# asserv1.net
KiCad netlist of a schematic drawn in Altium Designer
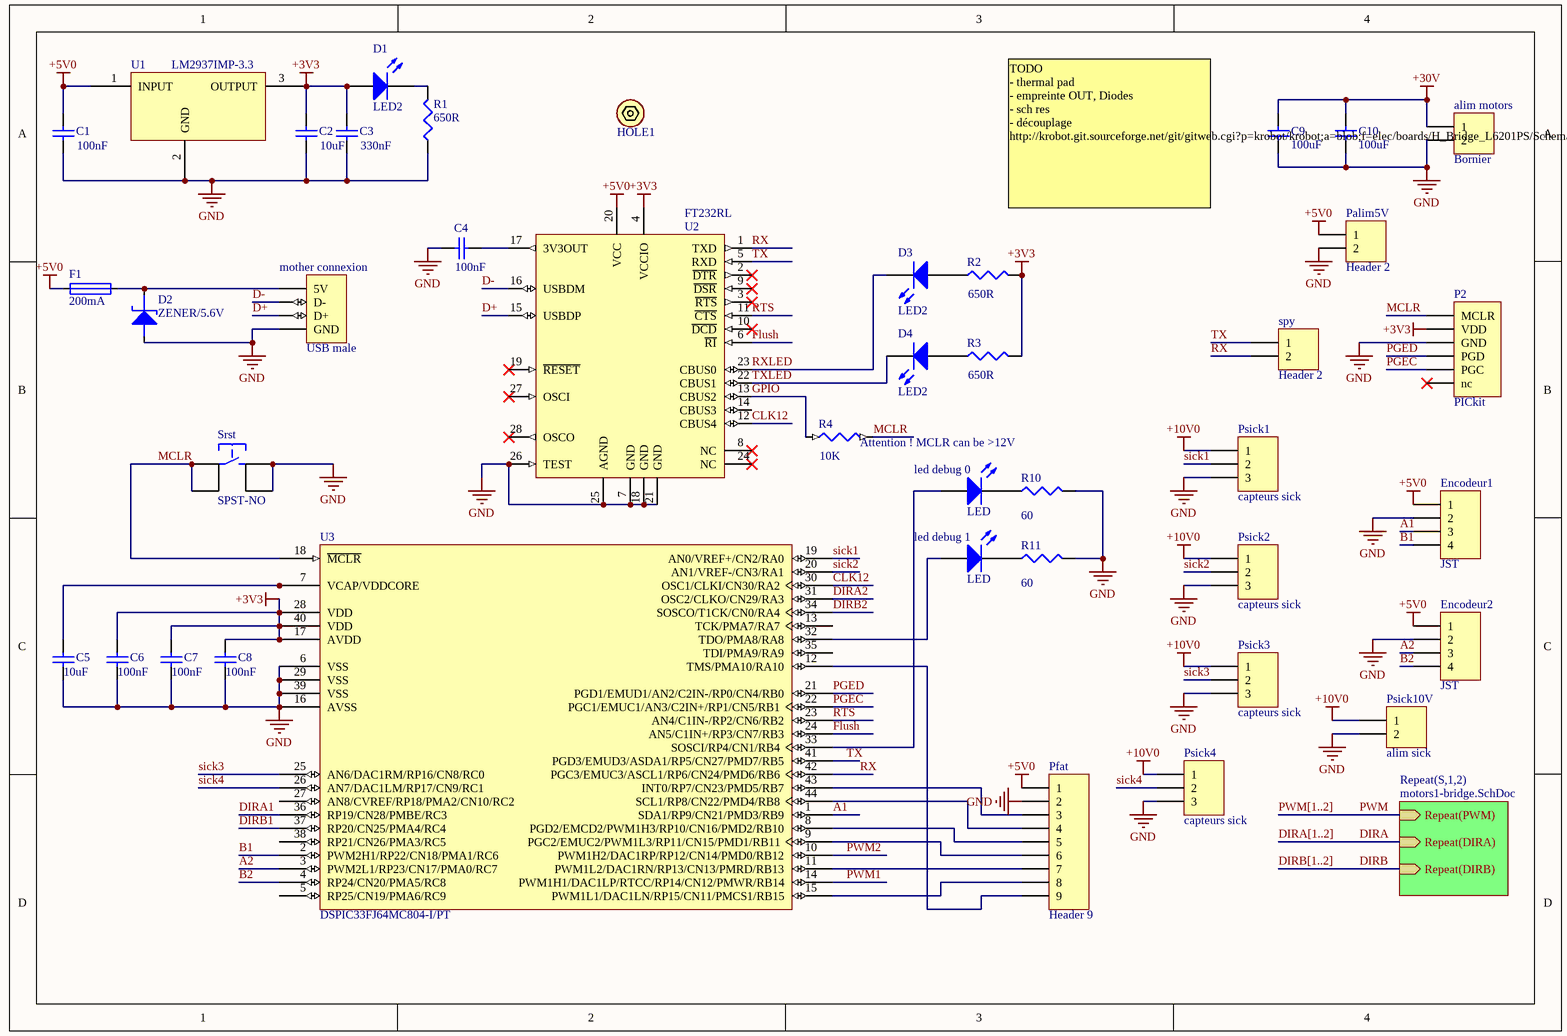
[diagram p0: asserv1.SchDoc]

(export (version "E")
  (design (tool "Eeschema 10.0.6"))
  (components
    (comp (ref "alim motors")
      (value "Bornier")
      (footprint "Bornier male coude 2 voies")
      (description "Header, 2-Pin")
      (fields (field (name "PUBLISHER") "Altium Limited"))
      (libsource (lib "7Robot") (part "Header 2"))
    )
    (comp (ref "C1")
      (value "100nF")
      (footprint "C0805C")
      (description "Capacitor (Semiconductor SIM Model)")
      (fields (field (name "PUBLISHER") "Altium Limited"))
      (libsource (lib "Miscellaneous Devices") (part "Cap Semi"))
    )
    (comp (ref "C2")
      (value "10uF")
      (footprint "C0805C")
      (description "Capacitor (Semiconductor SIM Model)")
      (fields (field (name "PUBLISHER") "Altium Limited"))
      (libsource (lib "Miscellaneous Devices") (part "Cap Semi"))
    )
    (comp (ref "C3")
      (value "330nF")
      (footprint "C0805C")
      (description "Capacitor (Semiconductor SIM Model)")
      (fields (field (name "PUBLISHER") "Altium Limited"))
      (libsource (lib "Miscellaneous Devices") (part "Cap Semi"))
    )
    (comp (ref "C4")
      (value "100nF")
      (footprint "C0805C")
      (description "Capacitor (Semiconductor SIM Model)")
      (fields (field (name "PUBLISHER") "Altium Limited"))
      (libsource (lib "Miscellaneous Devices") (part "Cap Semi"))
    )
    (comp (ref "C5")
      (value "10uF")
      (footprint "C0805C")
      (description "Capacitor (Semiconductor SIM Model)")
      (fields (field (name "PUBLISHER") "Altium Limited"))
      (libsource (lib "Miscellaneous Devices") (part "Cap Semi"))
    )
    (comp (ref "C6")
      (value "100nF")
      (footprint "C0805C")
      (description "Capacitor (Semiconductor SIM Model)")
      (fields (field (name "PUBLISHER") "Altium Limited"))
      (libsource (lib "Miscellaneous Devices") (part "Cap Semi"))
    )
    (comp (ref "C7")
      (value "100nF")
      (footprint "C0805C")
      (description "Capacitor (Semiconductor SIM Model)")
      (fields (field (name "PUBLISHER") "Altium Limited"))
      (libsource (lib "Miscellaneous Devices") (part "Cap Semi"))
    )
    (comp (ref "C8")
      (value "100nF")
      (footprint "C0805C")
      (description "Capacitor (Semiconductor SIM Model)")
      (fields (field (name "PUBLISHER") "Altium Limited"))
      (libsource (lib "Miscellaneous Devices") (part "Cap Semi"))
    )
    (comp (ref "C9")
      (value "100uF")
      (footprint "Capacitor axial leaded")
      (description "Capacitor")
      (fields (field (name "Comment") "CAP") (field (name "PUBLISHER") "Altium Limited"))
      (libsource (lib "7Robot") (part "CAP"))
    )
    (comp (ref "C10")
      (value "100uF")
      (footprint "Capacitor axial leaded")
      (description "Capacitor")
      (fields (field (name "Comment") "CAP") (field (name "PUBLISHER") "Altium Limited"))
      (libsource (lib "7Robot") (part "CAP"))
    )
    (comp (ref "D1")
      (value "LED2")
      (footprint "LED1206G")
      (description "Typical RED, GREEN, YELLOW, AMBER GaAs LED")
      (fields (field (name "PUBLISHER") "Altium Limited"))
      (libsource (lib "7Robot") (part "LED2"))
    )
    (comp (ref "D2")
      (value "ZENER/5.6V")
      (footprint "DSO-C2/X1.8")
      (description "ZENER")
      (libsource (lib "7Robot") (part "ZENER"))
    )
    (comp (ref "D3")
      (value "LED2")
      (footprint "LED1206Y")
      (description "Typical RED, GREEN, YELLOW, AMBER GaAs LED")
      (fields (field (name "PUBLISHER") "Altium Limited"))
      (libsource (lib "7Robot") (part "LED2"))
    )
    (comp (ref "D4")
      (value "LED2")
      (footprint "LED1206Y")
      (description "Typical RED, GREEN, YELLOW, AMBER GaAs LED")
      (fields (field (name "PUBLISHER") "Altium Limited"))
      (libsource (lib "7Robot") (part "LED2"))
    )
    (comp (ref "Encodeur1")
      (value "JST")
      (footprint "B4B-PH-K-S")
      (description "Header, 4-Pin")
      (fields (field (name "PUBLISHER") "Altium Limited"))
      (libsource (lib "Miscellaneous Connectors") (part "Header 4"))
    )
    (comp (ref "Encodeur2")
      (value "JST")
      (footprint "B4B-PH-K-S")
      (description "Header, 4-Pin")
      (fields (field (name "PUBLISHER") "Altium Limited"))
      (libsource (lib "Miscellaneous Connectors") (part "Header 4"))
    )
    (comp (ref "F1")
      (value "200mA")
      (footprint "Fuse Holder 5x20mm")
      (libsource (lib "gini_base_sch") (part "FUSE1"))
    )
    (comp (ref "HOLE1")
      (value "Hole")
      (footprint "SCREW")
      (description "Mounting Hole for screws")
      (libsource (lib "7Robot") (part "Hole"))
    )
    (comp (ref "led debug 0")
      (value "LED")
      (footprint "LED1206R")
      (description "Typical RED, GREEN, YELLOW, AMBER GaAs LED")
      (fields (field (name "PUBLISHER") "Altium Limited"))
      (libsource (lib "7Robot") (part "LED2"))
    )
    (comp (ref "led debug 1")
      (value "LED")
      (footprint "LED1206R")
      (description "Typical RED, GREEN, YELLOW, AMBER GaAs LED")
      (fields (field (name "PUBLISHER") "Altium Limited"))
      (libsource (lib "7Robot") (part "LED2"))
    )
    (comp (ref "mother connexion")
      (value "USB male")
      (footprint "USB SM2.5 Male")
      (description "USB Connector")
      (fields (field (name "PUBLISHER") "Altium Limited"))
      (libsource (lib "7Robot") (part "USB Con"))
    )
    (comp (ref "P2")
      (value "PICkit")
      (footprint "HDR1X6H")
      (description "Header, 6-Pin, Right Angle")
      (fields (field (name "PUBLISHER") "Altium Limited"))
      (libsource (lib "7Robot") (part "Header ICSP"))
    )
    (comp (ref "Palim5V")
      (value "Header 2")
      (footprint "Bornier male coude 2 voies")
      (description "Header, 2-Pin")
      (fields (field (name "PUBLISHER") "Altium Limited"))
      (libsource (lib "7Robot") (part "Header 2"))
    )
    (comp (ref "Pfat")
      (value "Header 9")
      (footprint "HDR1X9")
      (description "Header, 9-Pin")
      (fields (field (name "PUBLISHER") "Altium Limited"))
      (libsource (lib "7Robot") (part "Header 9"))
    )
    (comp (ref "Psick1")
      (value "capteurs sick")
      (footprint "HDR1X3")
      (description "Header, 3-Pin")
      (fields (field (name "PUBLISHER") "Altium Limited"))
      (libsource (lib "7Robot") (part "Header 3"))
    )
    (comp (ref "Psick2")
      (value "capteurs sick")
      (footprint "HDR1X3")
      (description "Header, 3-Pin")
      (fields (field (name "PUBLISHER") "Altium Limited"))
      (libsource (lib "7Robot") (part "Header 3"))
    )
    (comp (ref "Psick3")
      (value "capteurs sick")
      (footprint "HDR1X3")
      (description "Header, 3-Pin")
      (fields (field (name "PUBLISHER") "Altium Limited"))
      (libsource (lib "7Robot") (part "Header 3"))
    )
    (comp (ref "Psick4")
      (value "capteurs sick")
      (footprint "HDR1X3")
      (description "Header, 3-Pin")
      (fields (field (name "PUBLISHER") "Altium Limited"))
      (libsource (lib "7Robot") (part "Header 3"))
    )
    (comp (ref "Psick10V")
      (value "alim sick")
      (footprint "Bornier male coude 2 voies")
      (description "Header, 2-Pin")
      (fields (field (name "PUBLISHER") "Altium Limited"))
      (libsource (lib "7Robot") (part "Header 2"))
    )
    (comp (ref "R1")
      (value "650R")
      (footprint "C0805R")
      (description "Resistor")
      (fields (field (name "PUBLISHER") "Altium Limited"))
      (libsource (lib "Miscellaneous Devices") (part "Res3"))
    )
    (comp (ref "R2")
      (value "650R")
      (footprint "C0805R")
      (description "Resistor")
      (fields (field (name "PUBLISHER") "Altium Limited"))
      (libsource (lib "Miscellaneous Devices") (part "Res3"))
    )
    (comp (ref "R3")
      (value "650R")
      (footprint "C0805R")
      (description "Resistor")
      (fields (field (name "PUBLISHER") "Altium Limited"))
      (libsource (lib "Miscellaneous Devices") (part "Res3"))
    )
    (comp (ref "R4")
      (value "10K")
      (footprint "C0805R")
      (description "Resistor")
      (fields (field (name "PUBLISHER") "Altium Limited"))
      (libsource (lib "Miscellaneous Devices") (part "Res3"))
    )
    (comp (ref "R10")
      (value "60")
      (footprint "C0805R")
      (description "Resistor")
      (fields (field (name "PUBLISHER") "Altium Limited"))
      (libsource (lib "Miscellaneous Devices") (part "Res3"))
    )
    (comp (ref "R11")
      (value "60")
      (footprint "C0805R")
      (description "Resistor")
      (fields (field (name "PUBLISHER") "Altium Limited"))
      (libsource (lib "Miscellaneous Devices") (part "Res3"))
    )
    (comp (ref "spy")
      (value "Header 2")
      (footprint "HDR1X2")
      (description "Header, 2-Pin")
      (fields (field (name "PUBLISHER") "Altium Limited"))
      (libsource (lib "7Robot") (part "Header 2"))
    )
    (comp (ref "Srst")
      (value "SPST-NO")
      (footprint "SPST-NO")
      (description "Tactile Switch 7.3mm, SMD")
      (libsource (lib "7Robot") (part "SPST-NO"))
    )
    (comp (ref "U1")
      (value "LM2937IMP-3.3")
      (footprint "SOT223")
      (description "500 mA Low Dropout Regulator")
      (libsource (lib "7Robot") (part "LM2937IMP-3.3"))
    )
    (comp (ref "U2")
      (value "FT232RL")
      (footprint "SSOP-28_M")
      (description "USB UART Asynchronous Serial Data Transfer Chip, SSOP-28, Tube")
      (fields (field (name "PUBLISHER") "Altium Limited"))
      (libsource (lib "7Robot") (part "FT232RL"))
    )
    (comp (ref "U3")
      (value "DSPIC33FJ64MC804-I/PT")
      (footprint "TQFP-PT44_N")
      (fields (field (name "PUBLISHER") "Altium Limited"))
      (libsource (lib "7Robot") (part "DSPIC33FJ64MC804-I/PT"))
    )
  )
  (nets
    (net (code "1") (name "+3V3") (class "Default")
      (node (ref "C2") (pin "1") (pinfunction "1_1") (pintype "passive"))
      (node (ref "C3") (pin "1") (pinfunction "1_1") (pintype "passive"))
      (node (ref "C6") (pin "1") (pinfunction "1_1") (pintype "passive"))
      (node (ref "C7") (pin "1") (pinfunction "1_1") (pintype "passive"))
      (node (ref "C8") (pin "1") (pinfunction "1_1") (pintype "passive"))
      (node (ref "D1") (pin "1") (pinfunction "A_1") (pintype "passive"))
      (node (ref "P2") (pin "2") (pinfunction "VDD_2") (pintype "passive"))
      (node (ref "R2") (pin "2") (pinfunction "2_2") (pintype "passive"))
      (node (ref "R3") (pin "2") (pinfunction "2_2") (pintype "passive"))
      (node (ref "U1") (pin "3") (pinfunction "OUTPUT_3") (pintype "power_in"))
      (node (ref "U2") (pin "4") (pinfunction "VCCIO_4") (pintype "power_in"))
      (node (ref "U3") (pin "17") (pinfunction "AVDD_17") (pintype "power_in"))
      (node (ref "U3") (pin "28") (pinfunction "VDD_28") (pintype "power_in"))
      (node (ref "U3") (pin "40") (pinfunction "VDD_40") (pintype "power_in"))
    )
    (net (code "2") (name "+5V0") (class "Default")
      (node (ref "C1") (pin "1") (pinfunction "1_1") (pintype "passive"))
      (node (ref "Encodeur1") (pin "1") (pinfunction "1_1") (pintype "passive"))
      (node (ref "Encodeur2") (pin "1") (pinfunction "1_1") (pintype "passive"))
      (node (ref "F1") (pin "1") (pinfunction "1_1") (pintype "passive"))
      (node (ref "Palim5V") (pin "1") (pinfunction "1_1") (pintype "passive"))
      (node (ref "Pfat") (pin "1") (pinfunction "1_1") (pintype "passive"))
      (node (ref "U1") (pin "1") (pinfunction "INPUT_1") (pintype "power_in"))
      (node (ref "U2") (pin "20") (pinfunction "VCC_20") (pintype "power_in"))
    )
    (net (code "3") (name "+10V0") (class "Default")
      (node (ref "Psick1") (pin "1") (pinfunction "1_1") (pintype "passive"))
      (node (ref "Psick10V") (pin "1") (pinfunction "1_1") (pintype "passive"))
      (node (ref "Psick2") (pin "1") (pinfunction "1_1") (pintype "passive"))
      (node (ref "Psick3") (pin "1") (pinfunction "1_1") (pintype "passive"))
      (node (ref "Psick4") (pin "1") (pinfunction "1_1") (pintype "passive"))
    )
    (net (code "4") (name "+30V") (class "Default")
      (node (ref "C10") (pin "2") (pinfunction "2_2") (pintype "passive"))
      (node (ref "C9") (pin "2") (pinfunction "2_2") (pintype "passive"))
      (node (ref "alim motors") (pin "1") (pinfunction "1_1") (pintype "passive"))
    )
    (net (code "5") (name "/A1") (class "Default")
      (node (ref "Encodeur1") (pin "3") (pinfunction "3_3") (pintype "passive"))
      (node (ref "U3") (pin "1") (pinfunction "SDA1/RP9/CN21/PMD3/RB9_1") (pintype "bidirectional"))
    )
    (net (code "6") (name "/A2") (class "Default")
      (node (ref "Encodeur2") (pin "3") (pinfunction "3_3") (pintype "passive"))
      (node (ref "U3") (pin "3") (pinfunction "PWM2L1/RP23/CN17/PMA0/RC7_3") (pintype "bidirectional"))
    )
    (net (code "7") (name "/B1") (class "Default")
      (node (ref "Encodeur1") (pin "4") (pinfunction "4_4") (pintype "passive"))
      (node (ref "U3") (pin "2") (pinfunction "PWM2H1/RP22/CN18/PMA1/RC6_2") (pintype "bidirectional"))
    )
    (net (code "8") (name "/B2") (class "Default")
      (node (ref "Encodeur2") (pin "4") (pinfunction "4_4") (pintype "passive"))
      (node (ref "U3") (pin "4") (pinfunction "RP24/CN20/PMA5/RC8_4") (pintype "bidirectional"))
    )
    (net (code "9") (name "/CLK12") (class "Default")
      (node (ref "U2") (pin "12") (pinfunction "CBUS4_12") (pintype "bidirectional"))
      (node (ref "U3") (pin "30") (pinfunction "OSC1/CLKI/CN30/RA2_30") (pintype "bidirectional"))
    )
    (net (code "10") (name "/D+") (class "Default")
      (node (ref "U2") (pin "15") (pinfunction "USBDP_15") (pintype "bidirectional"))
      (node (ref "mother connexion") (pin "3") (pinfunction "D+_3") (pintype "bidirectional"))
    )
    (net (code "11") (name "/D-") (class "Default")
      (node (ref "U2") (pin "16") (pinfunction "USBDM_16") (pintype "bidirectional"))
      (node (ref "mother connexion") (pin "2") (pinfunction "D-_2") (pintype "bidirectional"))
    )
    (net (code "13") (name "/DIRA1") (class "Default")
      (node (ref "U3") (pin "36") (pinfunction "RP19/CN28/PMBE/RC3_36") (pintype "bidirectional"))
    )
    (net (code "14") (name "/DIRA2") (class "Default")
      (node (ref "U3") (pin "31") (pinfunction "OSC2/CLKO/CN29/RA3_31") (pintype "bidirectional"))
    )
    (net (code "17") (name "/DIRB1") (class "Default")
      (node (ref "U3") (pin "37") (pinfunction "RP20/CN25/PMA4/RC4_37") (pintype "bidirectional"))
    )
    (net (code "18") (name "/DIRB2") (class "Default")
      (node (ref "U3") (pin "34") (pinfunction "SOSCO/T1CK/CN0/RA4_34") (pintype "bidirectional"))
    )
    (net (code "20") (name "/Flush") (class "Default")
      (node (ref "U2") (pin "6") (pinfunction "~{RI}_6") (pintype "input"))
      (node (ref "U3") (pin "24") (pinfunction "AN5/C1IN+/RP3/CN7/RB3_24") (pintype "bidirectional"))
    )
    (net (code "21") (name "/GPIO") (class "Default")
      (node (ref "R4") (pin "1") (pinfunction "1_1") (pintype "passive"))
      (node (ref "U2") (pin "13") (pinfunction "CBUS2_13") (pintype "bidirectional"))
    )
    (net (code "22") (name "/MCLR") (class "Default")
      (node (ref "P2") (pin "1") (pinfunction "MCLR_1") (pintype "passive"))
      (node (ref "R4") (pin "2") (pinfunction "2_2") (pintype "passive"))
      (node (ref "Srst") (pin "1") (pintype "passive"))
      (node (ref "Srst") (pin "2") (pintype "passive"))
      (node (ref "U3") (pin "18") (pinfunction "~{MCLR}_18") (pintype "input"))
    )
    (net (code "23") (name "/PGEC") (class "Default")
      (node (ref "P2") (pin "5") (pinfunction "PGC_5") (pintype "passive"))
      (node (ref "U3") (pin "22") (pinfunction "PGC1/EMUC1/AN3/C2IN+/RP1/CN5/RB1_22") (pintype "bidirectional"))
    )
    (net (code "24") (name "/PGED") (class "Default")
      (node (ref "P2") (pin "4") (pinfunction "PGD_4") (pintype "passive"))
      (node (ref "U3") (pin "21") (pinfunction "PGD1/EMUD1/AN2/C2IN-/RP0/CN4/RB0_21") (pintype "bidirectional"))
    )
    (net (code "26") (name "/PWM1") (class "Default")
      (node (ref "U3") (pin "14") (pinfunction "PWM1H1/DAC1LP/RTCC/RP14/CN12/PMWR/RB14_14") (pintype "bidirectional"))
    )
    (net (code "27") (name "/PWM2") (class "Default")
      (node (ref "U3") (pin "10") (pinfunction "PWM1H2/DAC1RP/RP12/CN14/PMD0/RB12_10") (pintype "bidirectional"))
    )
    (net (code "29") (name "/RTS") (class "Default")
      (node (ref "U2") (pin "11") (pinfunction "~{CTS}_11") (pintype "input"))
      (node (ref "U3") (pin "23") (pinfunction "AN4/C1IN-/RP2/CN6/RB2_23") (pintype "bidirectional"))
    )
    (net (code "30") (name "/RX") (class "Default")
      (node (ref "U2") (pin "1") (pinfunction "TXD_1") (pintype "output"))
      (node (ref "U3") (pin "42") (pinfunction "PGC3/EMUC3/ASCL1/RP6/CN24/PMD6/RB6_42") (pintype "bidirectional"))
      (node (ref "spy") (pin "2") (pinfunction "2_2") (pintype "passive"))
    )
    (net (code "31") (name "/RXLED") (class "Default")
      (node (ref "D3") (pin "2") (pinfunction "K_2") (pintype "passive"))
      (node (ref "U2") (pin "23") (pinfunction "CBUS0_23") (pintype "bidirectional"))
    )
    (net (code "32") (name "/TX") (class "Default")
      (node (ref "U2") (pin "5") (pinfunction "RXD_5") (pintype "input"))
      (node (ref "U3") (pin "41") (pinfunction "PGD3/EMUD3/ASDA1/RP5/CN27/PMD7/RB5_41") (pintype "bidirectional"))
      (node (ref "spy") (pin "1") (pinfunction "1_1") (pintype "passive"))
    )
    (net (code "33") (name "/TXLED") (class "Default")
      (node (ref "D4") (pin "2") (pinfunction "K_2") (pintype "passive"))
      (node (ref "U2") (pin "22") (pinfunction "CBUS1_22") (pintype "bidirectional"))
    )
    (net (code "34") (name "/sick1") (class "Default")
      (node (ref "Psick1") (pin "2") (pinfunction "2_2") (pintype "passive"))
      (node (ref "U3") (pin "19") (pinfunction "AN0/VREF+/CN2/RA0_19") (pintype "bidirectional"))
    )
    (net (code "35") (name "/sick2") (class "Default")
      (node (ref "Psick2") (pin "2") (pinfunction "2_2") (pintype "passive"))
      (node (ref "U3") (pin "20") (pinfunction "AN1/VREF-/CN3/RA1_20") (pintype "bidirectional"))
    )
    (net (code "36") (name "/sick3") (class "Default")
      (node (ref "Psick3") (pin "2") (pinfunction "2_2") (pintype "passive"))
      (node (ref "U3") (pin "25") (pinfunction "AN6/DAC1RM/RP16/CN8/RC0_25") (pintype "bidirectional"))
    )
    (net (code "37") (name "/sick4") (class "Default")
      (node (ref "Psick4") (pin "2") (pinfunction "2_2") (pintype "passive"))
      (node (ref "U3") (pin "26") (pinfunction "AN7/DAC1LM/RP17/CN9/RC1_26") (pintype "bidirectional"))
    )
    (net (code "38") (name "GND") (class "Default")
      (node (ref "C1") (pin "2") (pinfunction "2_2") (pintype "passive"))
      (node (ref "C10") (pin "1") (pinfunction "1_1") (pintype "passive"))
      (node (ref "C2") (pin "2") (pinfunction "2_2") (pintype "passive"))
      (node (ref "C3") (pin "2") (pinfunction "2_2") (pintype "passive"))
      (node (ref "C4") (pin "1") (pinfunction "1_1") (pintype "passive"))
      (node (ref "C5") (pin "2") (pinfunction "2_2") (pintype "passive"))
      (node (ref "C6") (pin "2") (pinfunction "2_2") (pintype "passive"))
      (node (ref "C7") (pin "2") (pinfunction "2_2") (pintype "passive"))
      (node (ref "C8") (pin "2") (pinfunction "2_2") (pintype "passive"))
      (node (ref "C9") (pin "1") (pinfunction "1_1") (pintype "passive"))
      (node (ref "D2") (pin "A") (pinfunction "A_A") (pintype "passive"))
      (node (ref "Encodeur1") (pin "2") (pinfunction "2_2") (pintype "passive"))
      (node (ref "Encodeur2") (pin "2") (pinfunction "2_2") (pintype "passive"))
      (node (ref "P2") (pin "3") (pinfunction "GND_3") (pintype "passive"))
      (node (ref "Palim5V") (pin "2") (pinfunction "2_2") (pintype "passive"))
      (node (ref "Pfat") (pin "2") (pinfunction "2_2") (pintype "passive"))
      (node (ref "Psick1") (pin "3") (pinfunction "3_3") (pintype "passive"))
      (node (ref "Psick10V") (pin "2") (pinfunction "2_2") (pintype "passive"))
      (node (ref "Psick2") (pin "3") (pinfunction "3_3") (pintype "passive"))
      (node (ref "Psick3") (pin "3") (pinfunction "3_3") (pintype "passive"))
      (node (ref "Psick4") (pin "3") (pinfunction "3_3") (pintype "passive"))
      (node (ref "R1") (pin "1") (pinfunction "1_1") (pintype "passive"))
      (node (ref "R10") (pin "2") (pinfunction "2_2") (pintype "passive"))
      (node (ref "R11") (pin "2") (pinfunction "2_2") (pintype "passive"))
      (node (ref "Srst") (pin "3") (pintype "passive"))
      (node (ref "Srst") (pin "4") (pintype "passive"))
      (node (ref "U1") (pin "2") (pinfunction "GND_2") (pintype "power_in"))
      (node (ref "U2") (pin "18") (pinfunction "GND_18") (pintype "power_in"))
      (node (ref "U2") (pin "21") (pinfunction "GND_21") (pintype "power_in"))
      (node (ref "U2") (pin "25") (pinfunction "AGND_25") (pintype "power_in"))
      (node (ref "U2") (pin "26") (pinfunction "TEST_26") (pintype "input"))
      (node (ref "U2") (pin "7") (pinfunction "GND_7") (pintype "power_in"))
      (node (ref "U3") (pin "16") (pinfunction "AVSS_16") (pintype "power_in"))
      (node (ref "U3") (pin "29") (pinfunction "VSS_29") (pintype "power_in"))
      (node (ref "U3") (pin "39") (pinfunction "VSS_39") (pintype "power_in"))
      (node (ref "U3") (pin "6") (pinfunction "VSS_6") (pintype "power_in"))
      (node (ref "alim motors") (pin "2") (pinfunction "2_2") (pintype "passive"))
      (node (ref "mother connexion") (pin "4") (pinfunction "GND_4") (pintype "power_in"))
    )
    (net (code "39") (name "Net-(D1-K)") (class "Default")
      (node (ref "D1") (pin "2") (pinfunction "K_2") (pintype "passive"))
      (node (ref "R1") (pin "2") (pinfunction "2_2") (pintype "passive"))
    )
    (net (code "40") (name "Net-(D3-A)") (class "Default")
      (node (ref "D3") (pin "1") (pinfunction "A_1") (pintype "passive"))
      (node (ref "R2") (pin "1") (pinfunction "1_1") (pintype "passive"))
    )
    (net (code "41") (name "Net-(D4-A)") (class "Default")
      (node (ref "D4") (pin "1") (pinfunction "A_1") (pintype "passive"))
      (node (ref "R3") (pin "1") (pinfunction "1_1") (pintype "passive"))
    )
    (net (code "42") (name "Net-(U2-3V3OUT)") (class "Default")
      (node (ref "C4") (pin "2") (pinfunction "2_2") (pintype "passive"))
      (node (ref "U2") (pin "17") (pinfunction "3V3OUT_17") (pintype "output"))
    )
    (net (code "43") (name "Net-(U3-INT0{slash}RP7{slash}CN23{slash}PMD5{slash}RB7)") (class "Default")
      (node (ref "Pfat") (pin "3") (pinfunction "3_3") (pintype "passive"))
      (node (ref "U3") (pin "43") (pinfunction "INT0/RP7/CN23/PMD5/RB7_43") (pintype "bidirectional"))
    )
    (net (code "44") (name "Net-(U3-PGC2{slash}EMUC2{slash}PWM1L3{slash}RP11{slash}CN15{slash}PMD1{slash}RB11)") (class "Default")
      (node (ref "Pfat") (pin "6") (pinfunction "6_6") (pintype "passive"))
      (node (ref "U3") (pin "9") (pinfunction "PGC2/EMUC2/PWM1L3/RP11/CN15/PMD1/RB11_9") (pintype "bidirectional"))
    )
    (net (code "45") (name "Net-(U3-PGD2{slash}EMCD2{slash}PWM1H3{slash}RP10{slash}CN16{slash}PMD2{slash}RB10)") (class "Default")
      (node (ref "Pfat") (pin "5") (pinfunction "5_5") (pintype "passive"))
      (node (ref "U3") (pin "8") (pinfunction "PGD2/EMCD2/PWM1H3/RP10/CN16/PMD2/RB10_8") (pintype "bidirectional"))
    )
    (net (code "46") (name "Net-(U3-PWM1L1{slash}DAC1LN{slash}RP15{slash}CN11{slash}PMCS1{slash}RB15)") (class "Default")
      (node (ref "Pfat") (pin "8") (pinfunction "8_8") (pintype "passive"))
      (node (ref "U3") (pin "15") (pinfunction "PWM1L1/DAC1LN/RP15/CN11/PMCS1/RB15_15") (pintype "bidirectional"))
    )
    (net (code "47") (name "Net-(U3-PWM1L2{slash}DAC1RN{slash}RP13{slash}CN13{slash}PMRD{slash}RB13)") (class "Default")
      (node (ref "Pfat") (pin "7") (pinfunction "7_7") (pintype "passive"))
      (node (ref "U3") (pin "11") (pinfunction "PWM1L2/DAC1RN/RP13/CN13/PMRD/RB13_11") (pintype "bidirectional"))
    )
    (net (code "48") (name "Net-(U3-SCL1{slash}RP8{slash}CN22{slash}PMD4{slash}RB8)") (class "Default")
      (node (ref "Pfat") (pin "4") (pinfunction "4_4") (pintype "passive"))
      (node (ref "U3") (pin "44") (pinfunction "SCL1/RP8/CN22/PMD4/RB8_44") (pintype "bidirectional"))
    )
    (net (code "49") (name "Net-(U3-SOSCI{slash}RP4{slash}CN1{slash}RB4)") (class "Default")
      (node (ref "U3") (pin "33") (pinfunction "SOSCI/RP4/CN1/RB4_33") (pintype "bidirectional"))
      (node (ref "led debug 0") (pin "1") (pinfunction "A_1") (pintype "passive"))
    )
    (net (code "50") (name "Net-(U3-TDO{slash}PMA8{slash}RA8)") (class "Default")
      (node (ref "U3") (pin "32") (pinfunction "TDO/PMA8/RA8_32") (pintype "bidirectional"))
      (node (ref "led debug 1") (pin "1") (pinfunction "A_1") (pintype "passive"))
    )
    (net (code "51") (name "Net-(U3-TMS{slash}PMA10{slash}RA10)") (class "Default")
      (node (ref "Pfat") (pin "9") (pinfunction "9_9") (pintype "passive"))
      (node (ref "U3") (pin "12") (pinfunction "TMS/PMA10/RA10_12") (pintype "bidirectional"))
    )
    (net (code "52") (name "Net-(U3-VCAP{slash}VDDCORE)") (class "Default")
      (node (ref "C5") (pin "1") (pinfunction "1_1") (pintype "passive"))
      (node (ref "U3") (pin "7") (pinfunction "VCAP/VDDCORE_7") (pintype "power_in"))
    )
    (net (code "53") (name "Net-(led debug 0-K)") (class "Default")
      (node (ref "R10") (pin "1") (pinfunction "1_1") (pintype "passive"))
      (node (ref "led debug 0") (pin "2") (pinfunction "K_2") (pintype "passive"))
    )
    (net (code "54") (name "Net-(led debug 1-K)") (class "Default")
      (node (ref "R11") (pin "1") (pinfunction "1_1") (pintype "passive"))
      (node (ref "led debug 1") (pin "2") (pinfunction "K_2") (pintype "passive"))
    )
    (net (code "55") (name "Net-(mother connexion-5V)") (class "Default")
      (node (ref "D2") (pin "K") (pinfunction "K_K") (pintype "passive"))
      (node (ref "F1") (pin "2") (pinfunction "2_2") (pintype "passive"))
      (node (ref "mother connexion") (pin "1") (pinfunction "5V_1") (pintype "power_in"))
    )
    (net (code "56") (name "unconnected-(HOLE1-Hole-Pad1)") (class "Default")
      (node (ref "HOLE1") (pin "1") (pinfunction "Hole_1") (pintype "passive"))
    )
    (net (code "57") (name "unconnected-(P2-nc-Pad6)") (class "Default")
      (node (ref "P2") (pin "6") (pinfunction "nc_6") (pintype "passive+no_connect"))
    )
    (net (code "58") (name "unconnected-(U2-CBUS3-Pad14)") (class "Default")
      (node (ref "U2") (pin "14") (pinfunction "CBUS3_14") (pintype "bidirectional"))
    )
    (net (code "59") (name "unconnected-(U2-NC-Pad8)") (class "Default")
      (node (ref "U2") (pin "8") (pinfunction "NC_8") (pintype "passive+no_connect"))
    )
    (net (code "60") (name "unconnected-(U2-NC-Pad24)") (class "Default")
      (node (ref "U2") (pin "24") (pinfunction "NC_24") (pintype "passive+no_connect"))
    )
    (net (code "61") (name "unconnected-(U2-OSCI-Pad27)") (class "Default")
      (node (ref "U2") (pin "27") (pinfunction "OSCI_27") (pintype "input+no_connect"))
    )
    (net (code "62") (name "unconnected-(U2-OSCO-Pad28)") (class "Default")
      (node (ref "U2") (pin "28") (pinfunction "OSCO_28") (pintype "output+no_connect"))
    )
    (net (code "63") (name "unconnected-(U2-~{DCD}-Pad10)") (class "Default")
      (node (ref "U2") (pin "10") (pinfunction "~{DCD}_10") (pintype "input+no_connect"))
    )
    (net (code "64") (name "unconnected-(U2-~{DSR}-Pad9)") (class "Default")
      (node (ref "U2") (pin "9") (pinfunction "~{DSR}_9") (pintype "input+no_connect"))
    )
    (net (code "65") (name "unconnected-(U2-~{DTR}-Pad2)") (class "Default")
      (node (ref "U2") (pin "2") (pinfunction "~{DTR}_2") (pintype "output+no_connect"))
    )
    (net (code "66") (name "unconnected-(U2-~{RESET}-Pad19)") (class "Default")
      (node (ref "U2") (pin "19") (pinfunction "~{RESET}_19") (pintype "input+no_connect"))
    )
    (net (code "67") (name "unconnected-(U2-~{RTS}-Pad3)") (class "Default")
      (node (ref "U2") (pin "3") (pinfunction "~{RTS}_3") (pintype "output+no_connect"))
    )
    (net (code "68") (name "unconnected-(U3-AN8{slash}CVREF{slash}RP18{slash}PMA2{slash}CN10{slash}RC2-Pad27)") (class "Default")
      (node (ref "U3") (pin "27") (pinfunction "AN8/CVREF/RP18/PMA2/CN10/RC2_27") (pintype "bidirectional"))
    )
    (net (code "69") (name "unconnected-(U3-RP21{slash}CN26{slash}PMA3{slash}RC5-Pad38)") (class "Default")
      (node (ref "U3") (pin "38") (pinfunction "RP21/CN26/PMA3/RC5_38") (pintype "bidirectional"))
    )
    (net (code "70") (name "unconnected-(U3-RP25{slash}CN19{slash}PMA6{slash}RC9-Pad5)") (class "Default")
      (node (ref "U3") (pin "5") (pinfunction "RP25/CN19/PMA6/RC9_5") (pintype "bidirectional"))
    )
    (net (code "71") (name "unconnected-(U3-TCK{slash}PMA7{slash}RA7-Pad13)") (class "Default")
      (node (ref "U3") (pin "13") (pinfunction "TCK/PMA7/RA7_13") (pintype "bidirectional"))
    )
    (net (code "72") (name "unconnected-(U3-TDI{slash}PMA9{slash}RA9-Pad35)") (class "Default")
      (node (ref "U3") (pin "35") (pinfunction "TDI/PMA9/RA9_35") (pintype "bidirectional"))
    )
  )
)
